# sdcard.net
KiCad netlist of a schematic drawn in Altium Designer
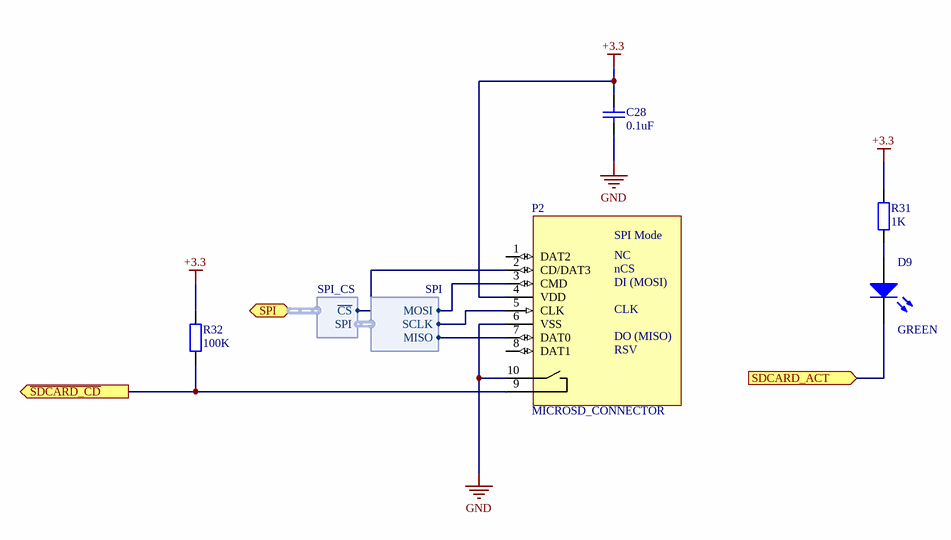
[diagram p0: sdcard.SchDoc]

(export (version "E")
  (design (tool "Eeschema 10.0.6"))
  (components
    (comp (ref "C28")
      (value "0.1uF")
      (footprint "C0603")
      (description "Capacitor")
      (fields (field (name "Comment") "Cap"))
      (libsource (lib "Miscellaneous Devices") (part "Cap"))
    )
    (comp (ref "D9")
      (value "GREEN")
      (footprint "LGQ971")
      (description "Typical RED, GREEN, YELLOW, AMBER GaAs LED")
      (libsource (lib "Miscellaneous Devices") (part "LED2"))
    )
    (comp (ref "P2")
      (value "MICROSD_CONNECTOR")
      (footprint "49225-0821")
      (description "MOLEX - 49225-0821 - CONNECTOR, MICRO SD, PUSH/PUSH, 8")
      (libsource (lib "MOLEX - 49225-0821 - CONNECTOR, MICRO SD") (part "MICROSD_CONNECTOR"))
    )
    (comp (ref "R31")
      (value "1K")
      (footprint "R0603")
      (description "Resistor")
      (fields (field (name "Comment") "Res"))
      (libsource (lib "Miscellaneous Devices") (part "Res2"))
    )
    (comp (ref "R32")
      (value "100K")
      (footprint "R0603")
      (description "Resistor")
      (fields (field (name "Comment") "Res"))
      (libsource (lib "Miscellaneous Devices") (part "Res2"))
    )
  )
  (nets
    (net (code "3") (name "+3.3") (class "Default")
      (node (ref "C28") (pin "1") (pinfunction "1_1") (pintype "passive"))
      (node (ref "P2") (pin "4") (pinfunction "VDD_4") (pintype "power_in"))
      (node (ref "R31") (pin "2") (pinfunction "2_2") (pintype "passive"))
      (node (ref "R32") (pin "2") (pinfunction "2_2") (pintype "passive"))
    )
    (net (code "4") (name "/SDCARD_ACT") (class "Default")
      (node (ref "D9") (pin "2") (pinfunction "K_2") (pintype "passive"))
    )
    (net (code "7") (name "/~{SDCARD_CD}") (class "Default")
      (node (ref "P2") (pin "9") (pintype "passive"))
      (node (ref "R32") (pin "1") (pinfunction "1_1") (pintype "passive"))
    )
    (net (code "8") (name "GND") (class "Default")
      (node (ref "C28") (pin "2") (pinfunction "2_2") (pintype "passive"))
      (node (ref "P2") (pin "10") (pintype "passive"))
      (node (ref "P2") (pin "6") (pinfunction "VSS_6") (pintype "power_in"))
    )
    (net (code "9") (name "Net-(D9-A)") (class "Default")
      (node (ref "D9") (pin "1") (pinfunction "A_1") (pintype "passive"))
      (node (ref "R31") (pin "1") (pinfunction "1_1") (pintype "passive"))
    )
    (net (code "10") (name "unconnected-(P2-CD{slash}DAT3-Pad2)") (class "Default")
      (node (ref "P2") (pin "2") (pinfunction "CD/DAT3_2") (pintype "bidirectional"))
    )
    (net (code "11") (name "unconnected-(P2-CLK-Pad5)") (class "Default")
      (node (ref "P2") (pin "5") (pinfunction "CLK_5") (pintype "input"))
    )
    (net (code "12") (name "unconnected-(P2-CMD-Pad3)") (class "Default")
      (node (ref "P2") (pin "3") (pinfunction "CMD_3") (pintype "bidirectional"))
    )
    (net (code "13") (name "unconnected-(P2-DAT0-Pad7)") (class "Default")
      (node (ref "P2") (pin "7") (pinfunction "DAT0_7") (pintype "bidirectional"))
    )
    (net (code "14") (name "unconnected-(P2-DAT1-Pad8)") (class "Default")
      (node (ref "P2") (pin "8") (pinfunction "DAT1_8") (pintype "bidirectional"))
    )
    (net (code "15") (name "unconnected-(P2-DAT2-Pad1)") (class "Default")
      (node (ref "P2") (pin "1") (pinfunction "DAT2_1") (pintype "bidirectional"))
    )
  )
)
